# C64_PSU_global.net
KiCad netlist of a schematic drawn in EAGLE
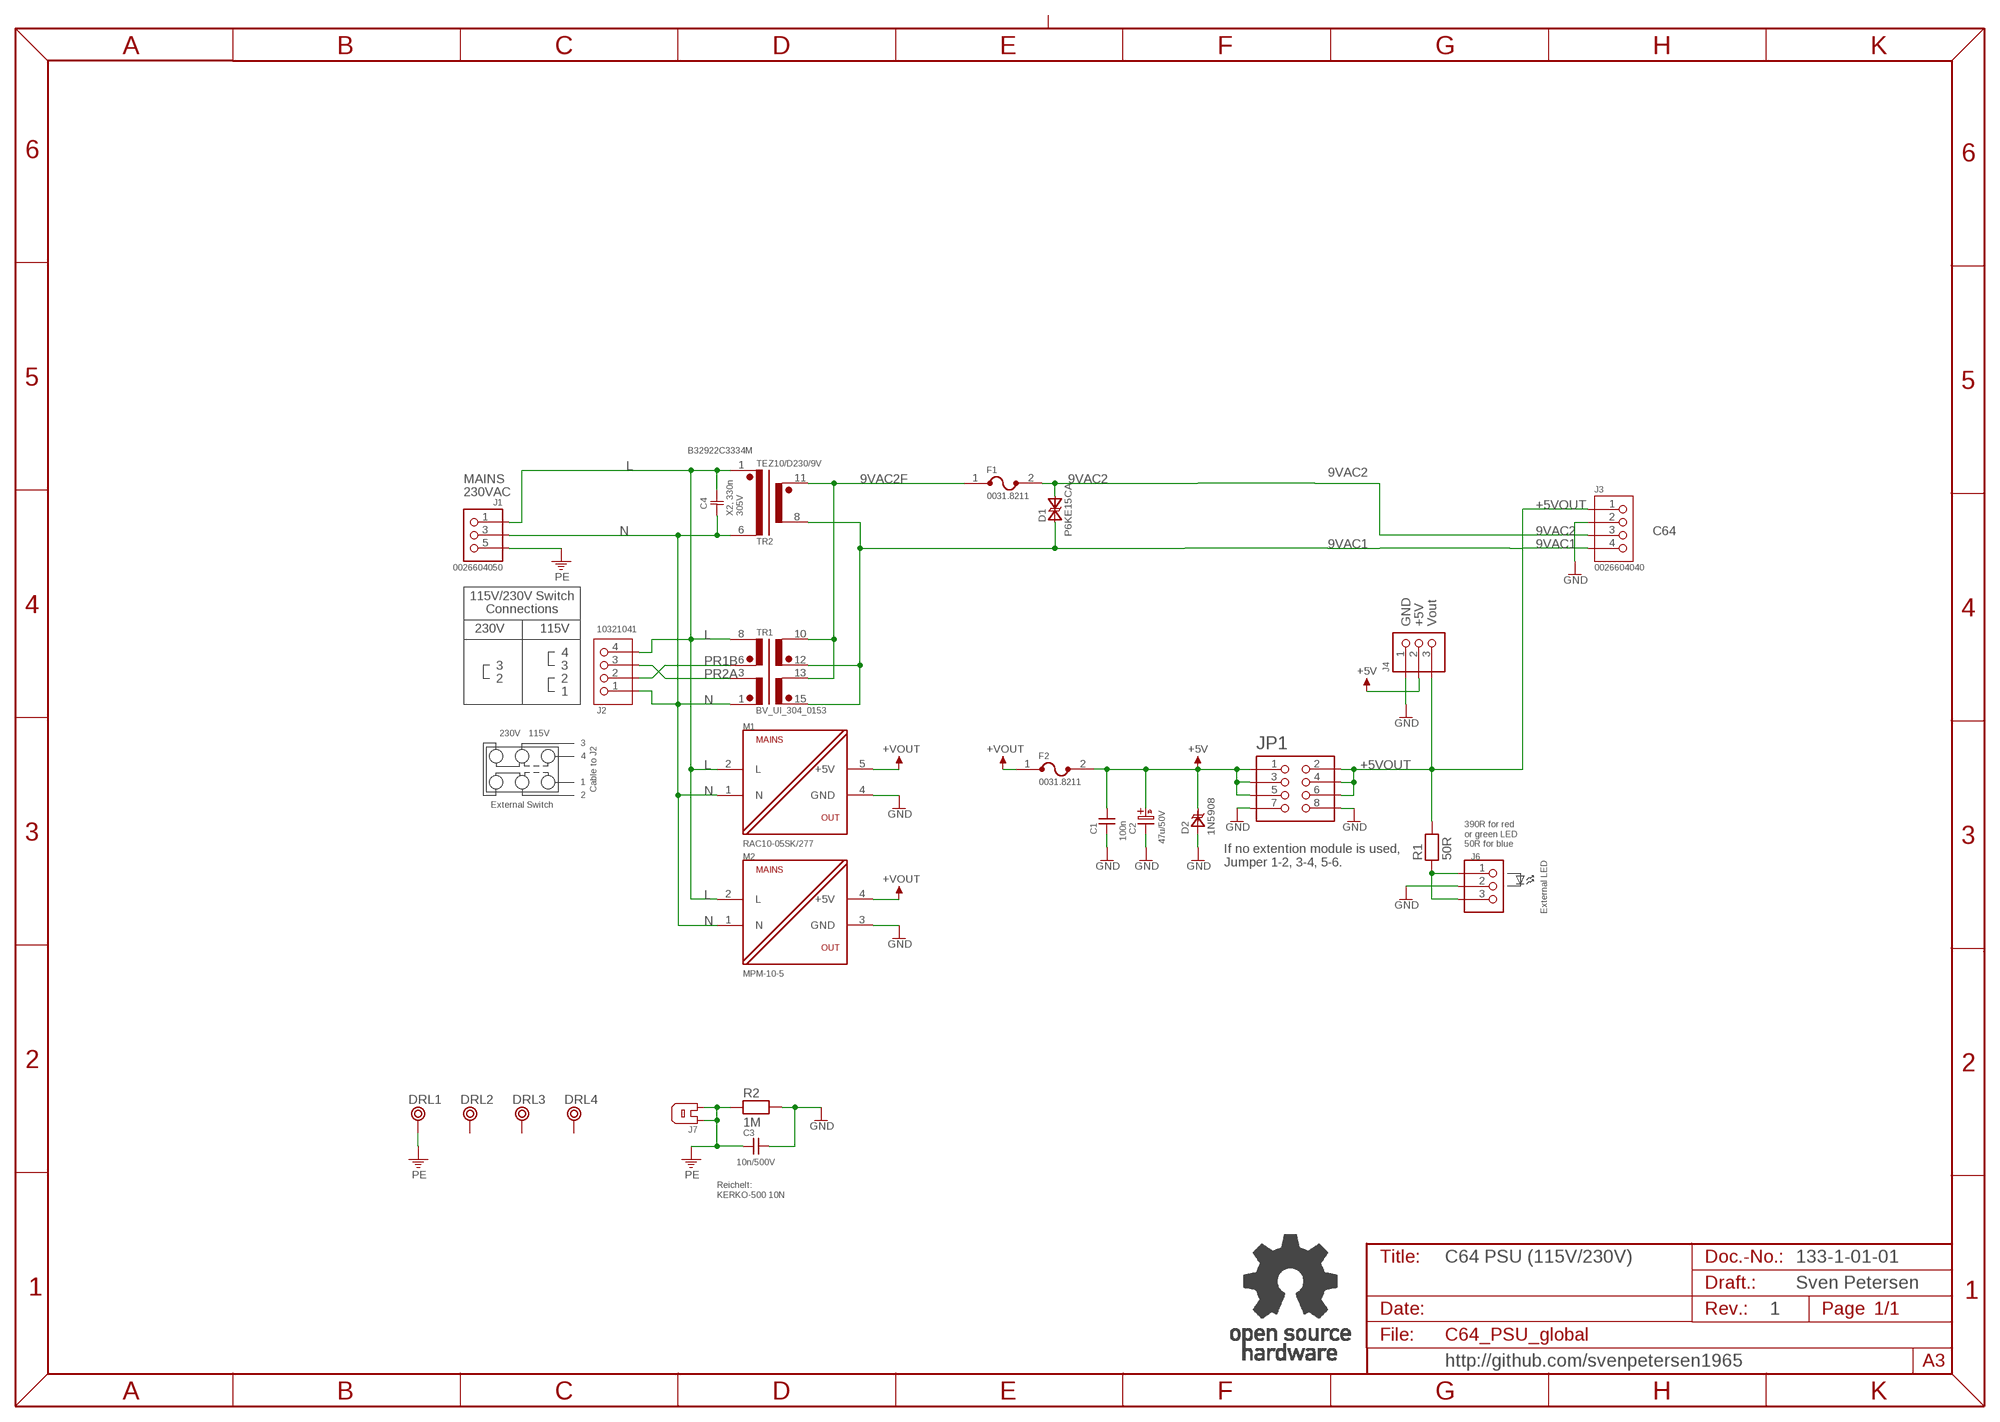
[diagram p0: schematic, sheet 1]

(export (version "E")
  (design (tool "Eeschema 10.0.6"))
  (components
    (comp (ref "C1")
      (value "100n")
      (footprint "eagle-import:C-2,5")
      (libsource (lib "eagle-import") (part "CAP01"))
    )
    (comp (ref "C2")
      (value "47u/50V")
      (footprint "eagle-import:C07_2,5")
      (libsource (lib "eagle-import") (part "C07/2,5"))
    )
    (comp (ref "C3")
      (value "10n/500V")
      (footprint "eagle-import:C-5")
      (libsource (lib "eagle-import") (part "CAP02"))
    )
    (comp (ref "C4")
      (value "B32922C3334M")
      (footprint "eagle-import:C-18X8-RM15")
      (libsource (lib "eagle-import") (part "X2--RM15-18X8"))
    )
    (comp (ref "D1")
      (value "P6KE15CA")
      (footprint "eagle-import:CB417NP")
      (libsource (lib "eagle-import") (part "P6KE15CA"))
    )
    (comp (ref "D2")
      (value "1N5908")
      (footprint "eagle-import:CB429")
      (libsource (lib "eagle-import") (part "1N5908"))
    )
    (comp (ref "DRL1")
      (value "BOHR3,5OR")
      (footprint "eagle-import:BOHR3,5_OHNE_RESTRICT")
      (libsource (lib "eagle-import") (part "BOHR3,5OR"))
    )
    (comp (ref "DRL2")
      (value "BOHR3,5")
      (footprint "eagle-import:BOHR3,5")
      (libsource (lib "eagle-import") (part "BOHR3,5"))
    )
    (comp (ref "DRL3")
      (value "BOHR3,5")
      (footprint "eagle-import:BOHR3,5")
      (libsource (lib "eagle-import") (part "BOHR3,5"))
    )
    (comp (ref "DRL4")
      (value "BOHR3,5")
      (footprint "eagle-import:BOHR3,5")
      (libsource (lib "eagle-import") (part "BOHR3,5"))
    )
    (comp (ref "F1")
      (value "0031.8211")
      (footprint "eagle-import:0031.8211")
      (libsource (lib "eagle-import") (part "0031.8211"))
    )
    (comp (ref "F2")
      (value "0031.8211")
      (footprint "eagle-import:0031.8211")
      (libsource (lib "eagle-import") (part "0031.8211"))
    )
    (comp (ref "J1")
      (value "0026604050")
      (footprint "eagle-import:SPOX_3.96_5P3")
      (libsource (lib "eagle-import") (part "0026604050MOD"))
    )
    (comp (ref "J2")
      (value "10321041")
      (footprint "eagle-import:SPOX_5.08_4P")
      (libsource (lib "eagle-import") (part "10321041"))
    )
    (comp (ref "J3")
      (value "0026604040")
      (footprint "eagle-import:SPOX_3.96_4P")
      (libsource (lib "eagle-import") (part "0026604040"))
    )
    (comp (ref "J4")
      (value "6410-3P")
      (footprint "eagle-import:6410-3P")
      (libsource (lib "eagle-import") (part "6410-3P"))
    )
    (comp (ref "J6")
      (value "PINHD-1X3")
      (footprint "eagle-import:1X03")
      (libsource (lib "eagle-import") (part "PINHD-1X3"))
    )
    (comp (ref "J7")
      (value "FLA6,3")
      (footprint "eagle-import:FLA6,3")
      (libsource (lib "eagle-import") (part "FLA6,3"))
    )
    (comp (ref "JP1")
      (value "PINHD-2X4")
      (footprint "eagle-import:2X04")
      (libsource (lib "eagle-import") (part "PINHD-2X4"))
    )
    (comp (ref "M1")
      (value "RAC10-05SK/277")
      (footprint "eagle-import:RAC10-K_277")
      (libsource (lib "eagle-import") (part "RAC10-05SK/277"))
    )
    (comp (ref "M2")
      (value "MPM-10-5")
      (footprint "eagle-import:MPM10")
      (libsource (lib "eagle-import") (part "MPM-10-5"))
    )
    (comp (ref "R1")
      (value "50R")
      (footprint "eagle-import:R-10")
      (libsource (lib "eagle-import") (part "RES04"))
    )
    (comp (ref "R2")
      (value "1M")
      (footprint "eagle-import:R-10")
      (libsource (lib "eagle-import") (part "RES04"))
    )
    (comp (ref "TR1")
      (value "BV_UI_304_0153")
      (footprint "eagle-import:UI30")
      (libsource (lib "eagle-import") (part "BV_UI_304_0153"))
    )
    (comp (ref "TR2")
      (value "TEZ10/D230/9V")
      (footprint "eagle-import:TEZ10")
      (libsource (lib "eagle-import") (part "TEZ10/D230/9V"))
    )
    (comp (ref "U$25")
      (value "OPEN_SOURCE_HW")
      (footprint "eagle-import:OPENHW")
      (libsource (lib "eagle-import") (part "OPEN_SOURCE_HW"))
    )
  )
  (nets
    (net (code "1") (name "+5V") (class "Default")
      (node (ref "C1") (pin "2") (pinfunction "2_2") (pintype "passive"))
      (node (ref "C2") (pin "A") (pinfunction "+_A") (pintype "passive"))
      (node (ref "D2") (pin "K") (pinfunction "K_K") (pintype "passive"))
      (node (ref "F2") (pin "2") (pinfunction "2_2") (pintype "passive"))
      (node (ref "J4") (pin "2") (pinfunction "2_2") (pintype "passive"))
      (node (ref "JP1") (pin "1") (pinfunction "1_1") (pintype "passive"))
      (node (ref "JP1") (pin "3") (pinfunction "3_3") (pintype "passive"))
      (node (ref "JP1") (pin "5") (pinfunction "5_5") (pintype "passive"))
    )
    (net (code "2") (name "+VOUT") (class "Default")
      (node (ref "F2") (pin "1") (pinfunction "1_1") (pintype "passive"))
      (node (ref "M1") (pin "5") (pinfunction "+5V_5") (pintype "power_in"))
      (node (ref "M2") (pin "4") (pinfunction "+5V_4") (pintype "power_in"))
    )
    (net (code "3") (name "/+5VOUT") (class "Default")
      (node (ref "J3") (pin "1") (pinfunction "1_1") (pintype "passive"))
      (node (ref "J4") (pin "3") (pinfunction "3_3") (pintype "passive"))
      (node (ref "JP1") (pin "2") (pinfunction "2_2") (pintype "passive"))
      (node (ref "JP1") (pin "4") (pinfunction "4_4") (pintype "passive"))
      (node (ref "JP1") (pin "6") (pinfunction "6_6") (pintype "passive"))
      (node (ref "R1") (pin "2") (pinfunction "2_2") (pintype "passive"))
    )
    (net (code "4") (name "/9VAC1") (class "Default")
      (node (ref "D1") (pin "A") (pinfunction "A1_A") (pintype "passive"))
      (node (ref "J3") (pin "4") (pinfunction "4_4") (pintype "passive"))
      (node (ref "TR1") (pin "12") (pinfunction "SEC1B_12") (pintype "passive"))
      (node (ref "TR1") (pin "15") (pinfunction "SEC2B_15") (pintype "passive"))
      (node (ref "TR2") (pin "8") (pinfunction "SEC11_8") (pintype "passive"))
    )
    (net (code "5") (name "/9VAC2") (class "Default")
      (node (ref "D1") (pin "K") (pinfunction "A2_K") (pintype "passive"))
      (node (ref "F1") (pin "2") (pinfunction "2_2") (pintype "passive"))
      (node (ref "J3") (pin "3") (pinfunction "3_3") (pintype "passive"))
    )
    (net (code "6") (name "/9VAC2F") (class "Default")
      (node (ref "F1") (pin "1") (pinfunction "1_1") (pintype "passive"))
      (node (ref "TR1") (pin "10") (pinfunction "SEC1A_10") (pintype "passive"))
      (node (ref "TR1") (pin "13") (pinfunction "SEC2A_13") (pintype "passive"))
      (node (ref "TR2") (pin "11") (pinfunction "SEC12_11") (pintype "passive"))
    )
    (net (code "7") (name "/L") (class "Default")
      (node (ref "C4") (pin "2") (pinfunction "2_2") (pintype "passive"))
      (node (ref "J1") (pin "1") (pinfunction "1_1") (pintype "passive"))
      (node (ref "J2") (pin "4") (pinfunction "4_4") (pintype "passive"))
      (node (ref "M1") (pin "2") (pinfunction "L_2") (pintype "power_in"))
      (node (ref "M2") (pin "2") (pinfunction "L_2") (pintype "power_in"))
      (node (ref "TR1") (pin "8") (pinfunction "PRI1A_8") (pintype "passive"))
      (node (ref "TR2") (pin "1") (pinfunction "PRI2_1") (pintype "passive"))
    )
    (net (code "8") (name "/N") (class "Default")
      (node (ref "C4") (pin "1") (pinfunction "1_1") (pintype "passive"))
      (node (ref "J1") (pin "3") (pinfunction "2_3") (pintype "passive"))
      (node (ref "J2") (pin "1") (pinfunction "1_1") (pintype "passive"))
      (node (ref "M1") (pin "1") (pinfunction "N_1") (pintype "power_in"))
      (node (ref "M2") (pin "1") (pinfunction "N_1") (pintype "power_in"))
      (node (ref "TR1") (pin "1") (pinfunction "PRI2B_1") (pintype "passive"))
      (node (ref "TR2") (pin "6") (pinfunction "PRI1_6") (pintype "passive"))
    )
    (net (code "9") (name "/PR1B") (class "Default")
      (node (ref "J2") (pin "2") (pinfunction "2_2") (pintype "passive"))
      (node (ref "TR1") (pin "6") (pinfunction "PRI1B_6") (pintype "passive"))
    )
    (net (code "10") (name "/PR2A") (class "Default")
      (node (ref "J2") (pin "3") (pinfunction "3_3") (pintype "passive"))
      (node (ref "TR1") (pin "3") (pinfunction "PRI2A_3") (pintype "passive"))
    )
    (net (code "11") (name "GND") (class "Default")
      (node (ref "C1") (pin "1") (pinfunction "1_1") (pintype "passive"))
      (node (ref "C2") (pin "K") (pinfunction "-_K") (pintype "passive"))
      (node (ref "C3") (pin "2") (pinfunction "2_2") (pintype "passive"))
      (node (ref "D2") (pin "A") (pinfunction "A_A") (pintype "passive"))
      (node (ref "J3") (pin "2") (pinfunction "2_2") (pintype "passive"))
      (node (ref "J4") (pin "1") (pinfunction "1_1") (pintype "passive"))
      (node (ref "J6") (pin "2") (pinfunction "2_2") (pintype "passive"))
      (node (ref "JP1") (pin "7") (pinfunction "7_7") (pintype "passive"))
      (node (ref "JP1") (pin "8") (pinfunction "8_8") (pintype "passive"))
      (node (ref "M1") (pin "4") (pinfunction "GND_4") (pintype "power_in"))
      (node (ref "M2") (pin "3") (pinfunction "GND_3") (pintype "power_in"))
      (node (ref "R2") (pin "2") (pinfunction "2_2") (pintype "passive"))
    )
    (net (code "12") (name "Net-(J6-Pad1)") (class "Default")
      (node (ref "J6") (pin "1") (pinfunction "1_1") (pintype "passive"))
      (node (ref "J6") (pin "3") (pinfunction "3_3") (pintype "passive"))
      (node (ref "R1") (pin "1") (pinfunction "1_1") (pintype "passive"))
    )
    (net (code "13") (name "PE") (class "Default")
      (node (ref "C3") (pin "1") (pinfunction "1_1") (pintype "passive"))
      (node (ref "DRL1") (pin "P$1") (pinfunction "P$1_P$1") (pintype "passive"))
      (node (ref "J1") (pin "5") (pinfunction "3_5") (pintype "passive"))
      (node (ref "J7") (pin "1") (pinfunction "1_1") (pintype "passive"))
      (node (ref "J7") (pin "2") (pinfunction "2_2") (pintype "passive"))
      (node (ref "R2") (pin "1") (pinfunction "1_1") (pintype "passive"))
    )
    (net (code "14") (name "unconnected-(DRL2-PadP$1)") (class "Default")
      (node (ref "DRL2") (pin "P$1") (pinfunction "P$1_P$1") (pintype "passive"))
    )
    (net (code "15") (name "unconnected-(DRL3-PadP$1)") (class "Default")
      (node (ref "DRL3") (pin "P$1") (pinfunction "P$1_P$1") (pintype "passive"))
    )
    (net (code "16") (name "unconnected-(DRL4-PadP$1)") (class "Default")
      (node (ref "DRL4") (pin "P$1") (pinfunction "P$1_P$1") (pintype "passive"))
    )
  )
)
